# untitled.net
KiCad netlist of a schematic drawn in EAGLE
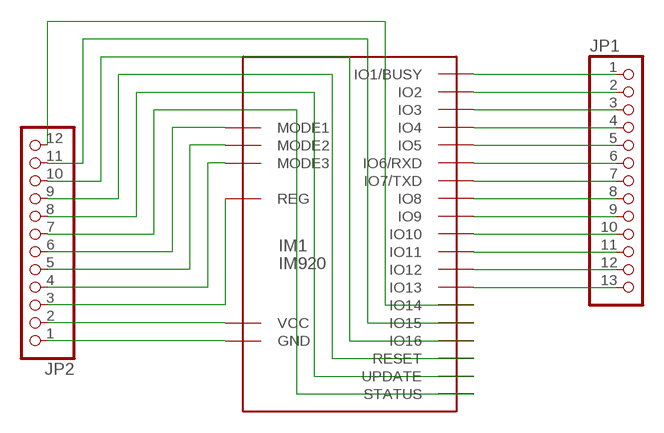
[diagram p0: schematic, sheet 1]

(export (version "E")
  (design (tool "Eeschema 10.0.6"))
  (components
    (comp (ref "IM1")
      (value "IM920")
      (footprint "eagle-import:IM920")
      (libsource (lib "eagle-import") (part "IM920"))
    )
    (comp (ref "JP1")
      (value "PINHD-1X13")
      (footprint "eagle-import:1X13")
      (libsource (lib "eagle-import") (part "PINHD-1X13"))
    )
    (comp (ref "JP2")
      (value "PINHD-1X12")
      (footprint "eagle-import:1X12")
      (libsource (lib "eagle-import") (part "PINHD-1X12"))
    )
  )
  (nets
    (net (code "1") (name "Net-(IM1-GND)") (class "Default")
      (node (ref "IM1") (pin "IO24") (pinfunction "GND_IO24") (pintype "bidirectional"))
      (node (ref "JP2") (pin "1") (pinfunction "1_1") (pintype "passive"))
    )
    (net (code "2") (name "Net-(IM1-IO1{slash}BUSY)") (class "Default")
      (node (ref "IM1") (pin "IO1") (pinfunction "IO1/BUSY_IO1") (pintype "bidirectional"))
      (node (ref "JP1") (pin "1") (pinfunction "1_1") (pintype "passive"))
    )
    (net (code "3") (name "Net-(IM1-IO6{slash}RXD)") (class "Default")
      (node (ref "IM1") (pin "IO6") (pinfunction "IO6/RXD_IO6") (pintype "bidirectional"))
      (node (ref "JP1") (pin "6") (pinfunction "6_6") (pintype "passive"))
    )
    (net (code "4") (name "Net-(IM1-IO7{slash}TXD)") (class "Default")
      (node (ref "IM1") (pin "IO7") (pinfunction "IO7/TXD_IO7") (pintype "bidirectional"))
      (node (ref "JP1") (pin "7") (pinfunction "7_7") (pintype "passive"))
    )
    (net (code "5") (name "Net-(IM1-MODE1)") (class "Default")
      (node (ref "IM1") (pin "IO17") (pinfunction "MODE1_IO17") (pintype "bidirectional"))
      (node (ref "JP2") (pin "6") (pinfunction "6_6") (pintype "passive"))
    )
    (net (code "6") (name "Net-(IM1-MODE2)") (class "Default")
      (node (ref "IM1") (pin "IO18") (pinfunction "MODE2_IO18") (pintype "bidirectional"))
      (node (ref "JP2") (pin "5") (pinfunction "5_5") (pintype "passive"))
    )
    (net (code "7") (name "Net-(IM1-MODE3)") (class "Default")
      (node (ref "IM1") (pin "IO19") (pinfunction "MODE3_IO19") (pintype "bidirectional"))
      (node (ref "JP2") (pin "4") (pinfunction "4_4") (pintype "passive"))
    )
    (net (code "8") (name "Net-(IM1-PadIO2)") (class "Default")
      (node (ref "IM1") (pin "IO2") (pinfunction "IO2_IO2") (pintype "bidirectional"))
      (node (ref "JP1") (pin "2") (pinfunction "2_2") (pintype "passive"))
    )
    (net (code "9") (name "Net-(IM1-PadIO3)") (class "Default")
      (node (ref "IM1") (pin "IO3") (pinfunction "IO3_IO3") (pintype "bidirectional"))
      (node (ref "JP1") (pin "3") (pinfunction "3_3") (pintype "passive"))
    )
    (net (code "10") (name "Net-(IM1-PadIO4)") (class "Default")
      (node (ref "IM1") (pin "IO4") (pinfunction "IO4_IO4") (pintype "bidirectional"))
      (node (ref "JP1") (pin "4") (pinfunction "4_4") (pintype "passive"))
    )
    (net (code "11") (name "Net-(IM1-PadIO5)") (class "Default")
      (node (ref "IM1") (pin "IO5") (pinfunction "IO5_IO5") (pintype "bidirectional"))
      (node (ref "JP1") (pin "5") (pinfunction "5_5") (pintype "passive"))
    )
    (net (code "12") (name "Net-(IM1-PadIO8)") (class "Default")
      (node (ref "IM1") (pin "IO8") (pinfunction "IO8_IO8") (pintype "bidirectional"))
      (node (ref "JP1") (pin "8") (pinfunction "8_8") (pintype "passive"))
    )
    (net (code "13") (name "Net-(IM1-PadIO9)") (class "Default")
      (node (ref "IM1") (pin "IO9") (pinfunction "IO9_IO9") (pintype "bidirectional"))
      (node (ref "JP1") (pin "9") (pinfunction "9_9") (pintype "passive"))
    )
    (net (code "14") (name "Net-(IM1-PadIO10)") (class "Default")
      (node (ref "IM1") (pin "IO10") (pinfunction "IO10_IO10") (pintype "bidirectional"))
      (node (ref "JP1") (pin "10") (pinfunction "10_10") (pintype "passive"))
    )
    (net (code "15") (name "Net-(IM1-PadIO11)") (class "Default")
      (node (ref "IM1") (pin "IO11") (pinfunction "IO11_IO11") (pintype "bidirectional"))
      (node (ref "JP1") (pin "11") (pinfunction "11_11") (pintype "passive"))
    )
    (net (code "16") (name "Net-(IM1-PadIO12)") (class "Default")
      (node (ref "IM1") (pin "IO12") (pinfunction "IO12_IO12") (pintype "bidirectional"))
      (node (ref "JP1") (pin "12") (pinfunction "12_12") (pintype "passive"))
    )
    (net (code "17") (name "Net-(IM1-PadIO13)") (class "Default")
      (node (ref "IM1") (pin "IO13") (pinfunction "IO13_IO13") (pintype "bidirectional"))
      (node (ref "JP1") (pin "13") (pinfunction "13_13") (pintype "passive"))
    )
    (net (code "18") (name "Net-(IM1-PadIO14)") (class "Default")
      (node (ref "IM1") (pin "IO14") (pinfunction "IO14_IO14") (pintype "bidirectional"))
      (node (ref "JP2") (pin "12") (pinfunction "12_12") (pintype "passive"))
    )
    (net (code "19") (name "Net-(IM1-PadIO15)") (class "Default")
      (node (ref "IM1") (pin "IO15") (pinfunction "IO15_IO15") (pintype "bidirectional"))
      (node (ref "JP2") (pin "11") (pinfunction "11_11") (pintype "passive"))
    )
    (net (code "20") (name "Net-(IM1-PadIO16)") (class "Default")
      (node (ref "IM1") (pin "IO16") (pinfunction "IO16_IO16") (pintype "bidirectional"))
      (node (ref "JP2") (pin "10") (pinfunction "10_10") (pintype "passive"))
    )
    (net (code "21") (name "Net-(IM1-REG)") (class "Default")
      (node (ref "IM1") (pin "IO22") (pinfunction "REG_IO22") (pintype "bidirectional"))
      (node (ref "JP2") (pin "3") (pinfunction "3_3") (pintype "passive"))
    )
    (net (code "22") (name "Net-(IM1-RESET)") (class "Default")
      (node (ref "IM1") (pin "IO25") (pinfunction "RESET_IO25") (pintype "bidirectional"))
      (node (ref "JP2") (pin "9") (pinfunction "9_9") (pintype "passive"))
    )
    (net (code "23") (name "Net-(IM1-STATUS)") (class "Default")
      (node (ref "IM1") (pin "IO21") (pinfunction "STATUS_IO21") (pintype "bidirectional"))
      (node (ref "JP2") (pin "7") (pinfunction "7_7") (pintype "passive"))
    )
    (net (code "24") (name "Net-(IM1-UPDATE)") (class "Default")
      (node (ref "IM1") (pin "IO20") (pinfunction "UPDATE_IO20") (pintype "bidirectional"))
      (node (ref "JP2") (pin "8") (pinfunction "8_8") (pintype "passive"))
    )
    (net (code "25") (name "Net-(IM1-VCC)") (class "Default")
      (node (ref "IM1") (pin "IO23") (pinfunction "VCC_IO23") (pintype "bidirectional"))
      (node (ref "JP2") (pin "2") (pinfunction "2_2") (pintype "passive"))
    )
  )
)
